# bbf-pots.net
KiCad netlist of a schematic drawn in EAGLE
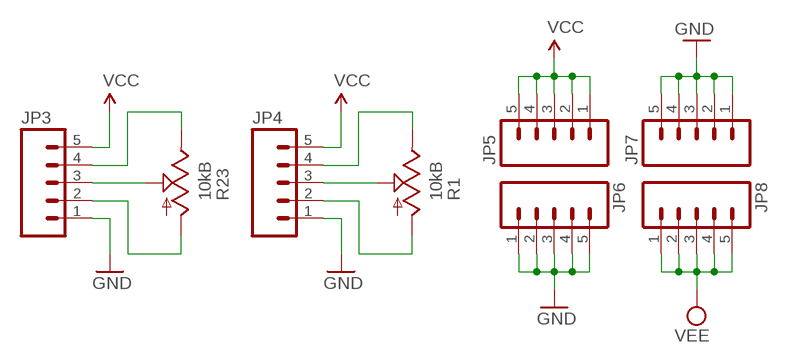
[diagram p0: schematic, sheet 1]

(export (version "E")
  (design (tool "Eeschema 10.0.6"))
  (components
    (comp (ref "JP3")
      (value "M05PTH")
      (footprint "eagle-import:1X05")
      (libsource (lib "eagle-import") (part "M05PTH"))
    )
    (comp (ref "JP4")
      (value "M05PTH")
      (footprint "eagle-import:1X05")
      (libsource (lib "eagle-import") (part "M05PTH"))
    )
    (comp (ref "JP5")
      (value "M05PTH")
      (footprint "eagle-import:1X05")
      (libsource (lib "eagle-import") (part "M05PTH"))
    )
    (comp (ref "JP6")
      (value "M05PTH")
      (footprint "eagle-import:1X05")
      (libsource (lib "eagle-import") (part "M05PTH"))
    )
    (comp (ref "JP7")
      (value "M05PTH")
      (footprint "eagle-import:1X05")
      (libsource (lib "eagle-import") (part "M05PTH"))
    )
    (comp (ref "JP8")
      (value "M05PTH")
      (footprint "eagle-import:1X05")
      (libsource (lib "eagle-import") (part "M05PTH"))
    )
    (comp (ref "R1")
      (value "10kB")
      (footprint "eagle-import:ALPS_POT_VERTICAL")
      (libsource (lib "eagle-import") (part "POT_USVERTICAL"))
    )
    (comp (ref "R23")
      (value "10kB")
      (footprint "eagle-import:ALPS_POT_VERTICAL")
      (libsource (lib "eagle-import") (part "POT_USVERTICAL"))
    )
  )
  (nets
    (net (code "1") (name "GND") (class "Default")
      (node (ref "JP3") (pin "1") (pinfunction "1_1") (pintype "passive"))
      (node (ref "JP4") (pin "1") (pinfunction "1_1") (pintype "passive"))
      (node (ref "JP6") (pin "1") (pinfunction "1_1") (pintype "passive"))
      (node (ref "JP6") (pin "2") (pinfunction "2_2") (pintype "passive"))
      (node (ref "JP6") (pin "3") (pinfunction "3_3") (pintype "passive"))
      (node (ref "JP6") (pin "4") (pinfunction "4_4") (pintype "passive"))
      (node (ref "JP6") (pin "5") (pinfunction "5_5") (pintype "passive"))
      (node (ref "JP7") (pin "1") (pinfunction "1_1") (pintype "passive"))
      (node (ref "JP7") (pin "2") (pinfunction "2_2") (pintype "passive"))
      (node (ref "JP7") (pin "3") (pinfunction "3_3") (pintype "passive"))
      (node (ref "JP7") (pin "4") (pinfunction "4_4") (pintype "passive"))
      (node (ref "JP7") (pin "5") (pinfunction "5_5") (pintype "passive"))
    )
    (net (code "2") (name "Net-(R1-A)") (class "Default")
      (node (ref "JP4") (pin "2") (pinfunction "2_2") (pintype "passive"))
      (node (ref "R1") (pin "P$3") (pinfunction "A_P$3") (pintype "passive"))
    )
    (net (code "3") (name "Net-(R1-E)") (class "Default")
      (node (ref "JP4") (pin "4") (pinfunction "4_4") (pintype "passive"))
      (node (ref "R1") (pin "P$1") (pinfunction "E_P$1") (pintype "passive"))
    )
    (net (code "4") (name "Net-(R1-S)") (class "Default")
      (node (ref "JP4") (pin "3") (pinfunction "3_3") (pintype "passive"))
      (node (ref "R1") (pin "P$2") (pinfunction "S_P$2") (pintype "passive"))
    )
    (net (code "5") (name "Net-(R23-A)") (class "Default")
      (node (ref "JP3") (pin "2") (pinfunction "2_2") (pintype "passive"))
      (node (ref "R23") (pin "P$3") (pinfunction "A_P$3") (pintype "passive"))
    )
    (net (code "6") (name "Net-(R23-E)") (class "Default")
      (node (ref "JP3") (pin "4") (pinfunction "4_4") (pintype "passive"))
      (node (ref "R23") (pin "P$1") (pinfunction "E_P$1") (pintype "passive"))
    )
    (net (code "7") (name "Net-(R23-S)") (class "Default")
      (node (ref "JP3") (pin "3") (pinfunction "3_3") (pintype "passive"))
      (node (ref "R23") (pin "P$2") (pinfunction "S_P$2") (pintype "passive"))
    )
    (net (code "8") (name "VCC") (class "Default")
      (node (ref "JP3") (pin "5") (pinfunction "5_5") (pintype "passive"))
      (node (ref "JP4") (pin "5") (pinfunction "5_5") (pintype "passive"))
      (node (ref "JP5") (pin "1") (pinfunction "1_1") (pintype "passive"))
      (node (ref "JP5") (pin "2") (pinfunction "2_2") (pintype "passive"))
      (node (ref "JP5") (pin "3") (pinfunction "3_3") (pintype "passive"))
      (node (ref "JP5") (pin "4") (pinfunction "4_4") (pintype "passive"))
      (node (ref "JP5") (pin "5") (pinfunction "5_5") (pintype "passive"))
    )
    (net (code "9") (name "VEE") (class "Default")
      (node (ref "JP8") (pin "1") (pinfunction "1_1") (pintype "passive"))
      (node (ref "JP8") (pin "2") (pinfunction "2_2") (pintype "passive"))
      (node (ref "JP8") (pin "3") (pinfunction "3_3") (pintype "passive"))
      (node (ref "JP8") (pin "4") (pinfunction "4_4") (pintype "passive"))
      (node (ref "JP8") (pin "5") (pinfunction "5_5") (pintype "passive"))
    )
  )
)
